# binary_watch_v0.net
KiCad netlist of a schematic drawn in EAGLE
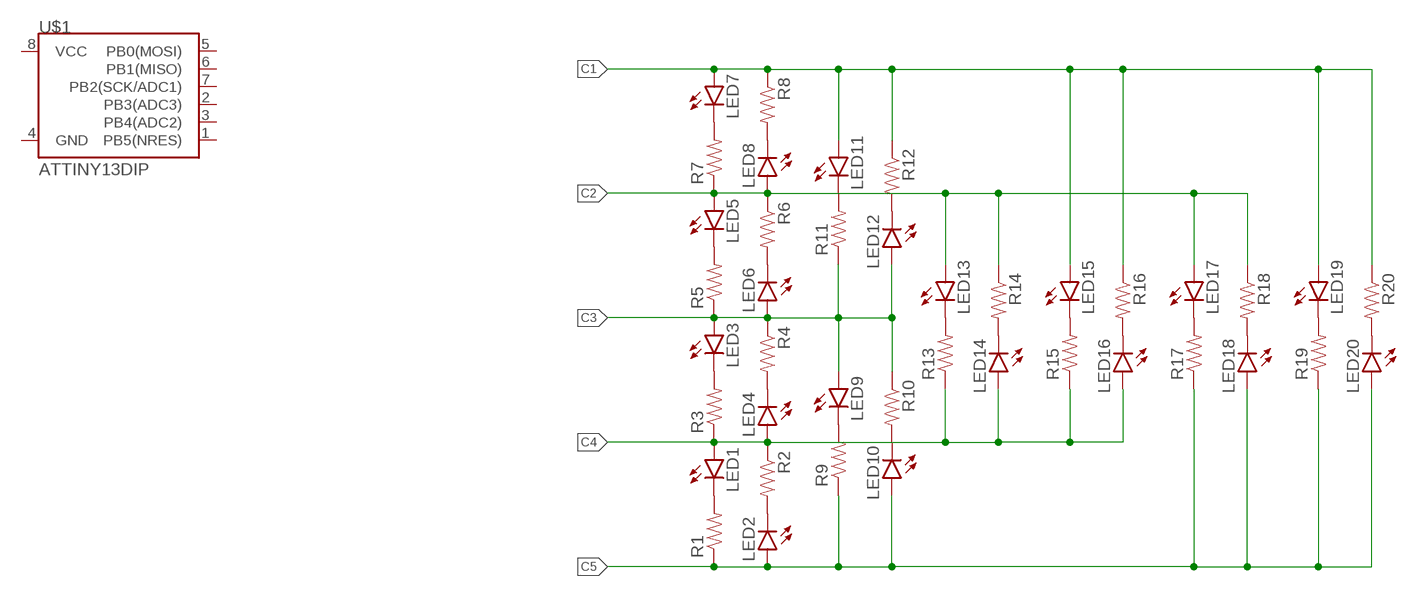
[diagram p0: schematic, sheet 1]

(export (version "E")
  (design (tool "Eeschema 10.0.6"))
  (components
    (comp (ref "LED1")
      (value "LED0603")
      (footprint "eagle-import:LED-0603")
      (libsource (lib "eagle-import") (part "LED0603"))
    )
    (comp (ref "LED2")
      (value "LED0603")
      (footprint "eagle-import:LED-0603")
      (libsource (lib "eagle-import") (part "LED0603"))
    )
    (comp (ref "LED3")
      (value "LED0603")
      (footprint "eagle-import:LED-0603")
      (libsource (lib "eagle-import") (part "LED0603"))
    )
    (comp (ref "LED4")
      (value "LED0603")
      (footprint "eagle-import:LED-0603")
      (libsource (lib "eagle-import") (part "LED0603"))
    )
    (comp (ref "LED5")
      (value "LED0603")
      (footprint "eagle-import:LED-0603")
      (libsource (lib "eagle-import") (part "LED0603"))
    )
    (comp (ref "LED6")
      (value "LED0603")
      (footprint "eagle-import:LED-0603")
      (libsource (lib "eagle-import") (part "LED0603"))
    )
    (comp (ref "LED7")
      (value "LED0603")
      (footprint "eagle-import:LED-0603")
      (libsource (lib "eagle-import") (part "LED0603"))
    )
    (comp (ref "LED8")
      (value "LED0603")
      (footprint "eagle-import:LED-0603")
      (libsource (lib "eagle-import") (part "LED0603"))
    )
    (comp (ref "LED9")
      (value "LED0603")
      (footprint "eagle-import:LED-0603")
      (libsource (lib "eagle-import") (part "LED0603"))
    )
    (comp (ref "LED10")
      (value "LED0603")
      (footprint "eagle-import:LED-0603")
      (libsource (lib "eagle-import") (part "LED0603"))
    )
    (comp (ref "LED11")
      (value "LED0603")
      (footprint "eagle-import:LED-0603")
      (libsource (lib "eagle-import") (part "LED0603"))
    )
    (comp (ref "LED12")
      (value "LED0603")
      (footprint "eagle-import:LED-0603")
      (libsource (lib "eagle-import") (part "LED0603"))
    )
    (comp (ref "LED13")
      (value "LED0603")
      (footprint "eagle-import:LED-0603")
      (libsource (lib "eagle-import") (part "LED0603"))
    )
    (comp (ref "LED14")
      (value "LED0603")
      (footprint "eagle-import:LED-0603")
      (libsource (lib "eagle-import") (part "LED0603"))
    )
    (comp (ref "LED15")
      (value "LED0603")
      (footprint "eagle-import:LED-0603")
      (libsource (lib "eagle-import") (part "LED0603"))
    )
    (comp (ref "LED16")
      (value "LED0603")
      (footprint "eagle-import:LED-0603")
      (libsource (lib "eagle-import") (part "LED0603"))
    )
    (comp (ref "LED17")
      (value "LED0603")
      (footprint "eagle-import:LED-0603")
      (libsource (lib "eagle-import") (part "LED0603"))
    )
    (comp (ref "LED18")
      (value "LED0603")
      (footprint "eagle-import:LED-0603")
      (libsource (lib "eagle-import") (part "LED0603"))
    )
    (comp (ref "LED19")
      (value "LED0603")
      (footprint "eagle-import:LED-0603")
      (libsource (lib "eagle-import") (part "LED0603"))
    )
    (comp (ref "LED20")
      (value "LED0603")
      (footprint "eagle-import:LED-0603")
      (libsource (lib "eagle-import") (part "LED0603"))
    )
    (comp (ref "R1")
      (value "RESISTOR0603-RES")
      (footprint "eagle-import:0603-RES")
      (libsource (lib "eagle-import") (part "RESISTOR0603-RES"))
    )
    (comp (ref "R2")
      (value "RESISTOR0603-RES")
      (footprint "eagle-import:0603-RES")
      (libsource (lib "eagle-import") (part "RESISTOR0603-RES"))
    )
    (comp (ref "R3")
      (value "RESISTOR0603-RES")
      (footprint "eagle-import:0603-RES")
      (libsource (lib "eagle-import") (part "RESISTOR0603-RES"))
    )
    (comp (ref "R4")
      (value "RESISTOR0603-RES")
      (footprint "eagle-import:0603-RES")
      (libsource (lib "eagle-import") (part "RESISTOR0603-RES"))
    )
    (comp (ref "R5")
      (value "RESISTOR0603-RES")
      (footprint "eagle-import:0603-RES")
      (libsource (lib "eagle-import") (part "RESISTOR0603-RES"))
    )
    (comp (ref "R6")
      (value "RESISTOR0603-RES")
      (footprint "eagle-import:0603-RES")
      (libsource (lib "eagle-import") (part "RESISTOR0603-RES"))
    )
    (comp (ref "R7")
      (value "RESISTOR0603-RES")
      (footprint "eagle-import:0603-RES")
      (libsource (lib "eagle-import") (part "RESISTOR0603-RES"))
    )
    (comp (ref "R8")
      (value "RESISTOR0603-RES")
      (footprint "eagle-import:0603-RES")
      (libsource (lib "eagle-import") (part "RESISTOR0603-RES"))
    )
    (comp (ref "R9")
      (value "RESISTOR0603-RES")
      (footprint "eagle-import:0603-RES")
      (libsource (lib "eagle-import") (part "RESISTOR0603-RES"))
    )
    (comp (ref "R10")
      (value "RESISTOR0603-RES")
      (footprint "eagle-import:0603-RES")
      (libsource (lib "eagle-import") (part "RESISTOR0603-RES"))
    )
    (comp (ref "R11")
      (value "RESISTOR0603-RES")
      (footprint "eagle-import:0603-RES")
      (libsource (lib "eagle-import") (part "RESISTOR0603-RES"))
    )
    (comp (ref "R12")
      (value "RESISTOR0603-RES")
      (footprint "eagle-import:0603-RES")
      (libsource (lib "eagle-import") (part "RESISTOR0603-RES"))
    )
    (comp (ref "R13")
      (value "RESISTOR0603-RES")
      (footprint "eagle-import:0603-RES")
      (libsource (lib "eagle-import") (part "RESISTOR0603-RES"))
    )
    (comp (ref "R14")
      (value "RESISTOR0603-RES")
      (footprint "eagle-import:0603-RES")
      (libsource (lib "eagle-import") (part "RESISTOR0603-RES"))
    )
    (comp (ref "R15")
      (value "RESISTOR0603-RES")
      (footprint "eagle-import:0603-RES")
      (libsource (lib "eagle-import") (part "RESISTOR0603-RES"))
    )
    (comp (ref "R16")
      (value "RESISTOR0603-RES")
      (footprint "eagle-import:0603-RES")
      (libsource (lib "eagle-import") (part "RESISTOR0603-RES"))
    )
    (comp (ref "R17")
      (value "RESISTOR0603-RES")
      (footprint "eagle-import:0603-RES")
      (libsource (lib "eagle-import") (part "RESISTOR0603-RES"))
    )
    (comp (ref "R18")
      (value "RESISTOR0603-RES")
      (footprint "eagle-import:0603-RES")
      (libsource (lib "eagle-import") (part "RESISTOR0603-RES"))
    )
    (comp (ref "R19")
      (value "RESISTOR0603-RES")
      (footprint "eagle-import:0603-RES")
      (libsource (lib "eagle-import") (part "RESISTOR0603-RES"))
    )
    (comp (ref "R20")
      (value "RESISTOR0603-RES")
      (footprint "eagle-import:0603-RES")
      (libsource (lib "eagle-import") (part "RESISTOR0603-RES"))
    )
    (comp (ref "U$1")
      (value "ATTINY13DIP")
      (footprint "eagle-import:DIP08")
      (libsource (lib "eagle-import") (part "ATTINY13DIP"))
    )
  )
  (nets
    (net (code "1") (name "C1") (class "Default")
      (node (ref "LED11") (pin "A") (pinfunction "A_A") (pintype "passive"))
      (node (ref "LED15") (pin "A") (pinfunction "A_A") (pintype "passive"))
      (node (ref "LED19") (pin "A") (pinfunction "A_A") (pintype "passive"))
      (node (ref "LED7") (pin "A") (pinfunction "A_A") (pintype "passive"))
      (node (ref "R12") (pin "1") (pinfunction "1_1") (pintype "passive"))
      (node (ref "R16") (pin "1") (pinfunction "1_1") (pintype "passive"))
      (node (ref "R20") (pin "1") (pinfunction "1_1") (pintype "passive"))
      (node (ref "R8") (pin "1") (pinfunction "1_1") (pintype "passive"))
    )
    (net (code "2") (name "C2") (class "Default")
      (node (ref "LED13") (pin "A") (pinfunction "A_A") (pintype "passive"))
      (node (ref "LED17") (pin "A") (pinfunction "A_A") (pintype "passive"))
      (node (ref "LED5") (pin "A") (pinfunction "A_A") (pintype "passive"))
      (node (ref "LED8") (pin "A") (pinfunction "A_A") (pintype "passive"))
      (node (ref "R14") (pin "1") (pinfunction "1_1") (pintype "passive"))
      (node (ref "R18") (pin "1") (pinfunction "1_1") (pintype "passive"))
      (node (ref "R6") (pin "1") (pinfunction "1_1") (pintype "passive"))
      (node (ref "R7") (pin "1") (pinfunction "1_1") (pintype "passive"))
    )
    (net (code "3") (name "C3") (class "Default")
      (node (ref "LED12") (pin "A") (pinfunction "A_A") (pintype "passive"))
      (node (ref "LED3") (pin "A") (pinfunction "A_A") (pintype "passive"))
      (node (ref "LED6") (pin "A") (pinfunction "A_A") (pintype "passive"))
      (node (ref "LED9") (pin "A") (pinfunction "A_A") (pintype "passive"))
      (node (ref "R10") (pin "1") (pinfunction "1_1") (pintype "passive"))
      (node (ref "R11") (pin "1") (pinfunction "1_1") (pintype "passive"))
      (node (ref "R4") (pin "1") (pinfunction "1_1") (pintype "passive"))
      (node (ref "R5") (pin "1") (pinfunction "1_1") (pintype "passive"))
    )
    (net (code "4") (name "C4") (class "Default")
      (node (ref "LED1") (pin "A") (pinfunction "A_A") (pintype "passive"))
      (node (ref "LED14") (pin "A") (pinfunction "A_A") (pintype "passive"))
      (node (ref "LED16") (pin "A") (pinfunction "A_A") (pintype "passive"))
      (node (ref "LED4") (pin "A") (pinfunction "A_A") (pintype "passive"))
      (node (ref "R13") (pin "1") (pinfunction "1_1") (pintype "passive"))
      (node (ref "R15") (pin "1") (pinfunction "1_1") (pintype "passive"))
      (node (ref "R2") (pin "1") (pinfunction "1_1") (pintype "passive"))
      (node (ref "R3") (pin "1") (pinfunction "1_1") (pintype "passive"))
    )
    (net (code "5") (name "C5") (class "Default")
      (node (ref "LED10") (pin "A") (pinfunction "A_A") (pintype "passive"))
      (node (ref "LED18") (pin "A") (pinfunction "A_A") (pintype "passive"))
      (node (ref "LED2") (pin "A") (pinfunction "A_A") (pintype "passive"))
      (node (ref "LED20") (pin "A") (pinfunction "A_A") (pintype "passive"))
      (node (ref "R1") (pin "1") (pinfunction "1_1") (pintype "passive"))
      (node (ref "R17") (pin "1") (pinfunction "1_1") (pintype "passive"))
      (node (ref "R19") (pin "1") (pinfunction "1_1") (pintype "passive"))
      (node (ref "R9") (pin "1") (pinfunction "1_1") (pintype "passive"))
    )
    (net (code "6") (name "Net-(LED1-PadC)") (class "Default")
      (node (ref "LED1") (pin "C") (pinfunction "C_C") (pintype "passive"))
      (node (ref "R1") (pin "2") (pinfunction "2_2") (pintype "passive"))
    )
    (net (code "7") (name "Net-(LED2-PadC)") (class "Default")
      (node (ref "LED2") (pin "C") (pinfunction "C_C") (pintype "passive"))
      (node (ref "R2") (pin "2") (pinfunction "2_2") (pintype "passive"))
    )
    (net (code "8") (name "Net-(LED3-PadC)") (class "Default")
      (node (ref "LED3") (pin "C") (pinfunction "C_C") (pintype "passive"))
      (node (ref "R3") (pin "2") (pinfunction "2_2") (pintype "passive"))
    )
    (net (code "9") (name "Net-(LED4-PadC)") (class "Default")
      (node (ref "LED4") (pin "C") (pinfunction "C_C") (pintype "passive"))
      (node (ref "R4") (pin "2") (pinfunction "2_2") (pintype "passive"))
    )
    (net (code "10") (name "Net-(LED5-PadC)") (class "Default")
      (node (ref "LED5") (pin "C") (pinfunction "C_C") (pintype "passive"))
      (node (ref "R5") (pin "2") (pinfunction "2_2") (pintype "passive"))
    )
    (net (code "11") (name "Net-(LED6-PadC)") (class "Default")
      (node (ref "LED6") (pin "C") (pinfunction "C_C") (pintype "passive"))
      (node (ref "R6") (pin "2") (pinfunction "2_2") (pintype "passive"))
    )
    (net (code "12") (name "Net-(LED7-PadC)") (class "Default")
      (node (ref "LED7") (pin "C") (pinfunction "C_C") (pintype "passive"))
      (node (ref "R7") (pin "2") (pinfunction "2_2") (pintype "passive"))
    )
    (net (code "13") (name "Net-(LED8-PadC)") (class "Default")
      (node (ref "LED8") (pin "C") (pinfunction "C_C") (pintype "passive"))
      (node (ref "R8") (pin "2") (pinfunction "2_2") (pintype "passive"))
    )
    (net (code "14") (name "Net-(LED9-PadC)") (class "Default")
      (node (ref "LED9") (pin "C") (pinfunction "C_C") (pintype "passive"))
      (node (ref "R9") (pin "2") (pinfunction "2_2") (pintype "passive"))
    )
    (net (code "15") (name "Net-(LED10-PadC)") (class "Default")
      (node (ref "LED10") (pin "C") (pinfunction "C_C") (pintype "passive"))
      (node (ref "R10") (pin "2") (pinfunction "2_2") (pintype "passive"))
    )
    (net (code "16") (name "Net-(LED11-PadC)") (class "Default")
      (node (ref "LED11") (pin "C") (pinfunction "C_C") (pintype "passive"))
      (node (ref "R11") (pin "2") (pinfunction "2_2") (pintype "passive"))
    )
    (net (code "17") (name "Net-(LED12-PadC)") (class "Default")
      (node (ref "LED12") (pin "C") (pinfunction "C_C") (pintype "passive"))
      (node (ref "R12") (pin "2") (pinfunction "2_2") (pintype "passive"))
    )
    (net (code "18") (name "Net-(LED13-PadC)") (class "Default")
      (node (ref "LED13") (pin "C") (pinfunction "C_C") (pintype "passive"))
      (node (ref "R13") (pin "2") (pinfunction "2_2") (pintype "passive"))
    )
    (net (code "19") (name "Net-(LED14-PadC)") (class "Default")
      (node (ref "LED14") (pin "C") (pinfunction "C_C") (pintype "passive"))
      (node (ref "R14") (pin "2") (pinfunction "2_2") (pintype "passive"))
    )
    (net (code "20") (name "Net-(LED15-PadC)") (class "Default")
      (node (ref "LED15") (pin "C") (pinfunction "C_C") (pintype "passive"))
      (node (ref "R15") (pin "2") (pinfunction "2_2") (pintype "passive"))
    )
    (net (code "21") (name "Net-(LED16-PadC)") (class "Default")
      (node (ref "LED16") (pin "C") (pinfunction "C_C") (pintype "passive"))
      (node (ref "R16") (pin "2") (pinfunction "2_2") (pintype "passive"))
    )
    (net (code "22") (name "Net-(LED17-PadC)") (class "Default")
      (node (ref "LED17") (pin "C") (pinfunction "C_C") (pintype "passive"))
      (node (ref "R17") (pin "2") (pinfunction "2_2") (pintype "passive"))
    )
    (net (code "23") (name "Net-(LED18-PadC)") (class "Default")
      (node (ref "LED18") (pin "C") (pinfunction "C_C") (pintype "passive"))
      (node (ref "R18") (pin "2") (pinfunction "2_2") (pintype "passive"))
    )
    (net (code "24") (name "Net-(LED19-PadC)") (class "Default")
      (node (ref "LED19") (pin "C") (pinfunction "C_C") (pintype "passive"))
      (node (ref "R19") (pin "2") (pinfunction "2_2") (pintype "passive"))
    )
    (net (code "25") (name "Net-(LED20-PadC)") (class "Default")
      (node (ref "LED20") (pin "C") (pinfunction "C_C") (pintype "passive"))
      (node (ref "R20") (pin "2") (pinfunction "2_2") (pintype "passive"))
    )
    (net (code "26") (name "unconnected-(U$1-GND-Pad4)") (class "Default")
      (node (ref "U$1") (pin "4") (pinfunction "GND_4") (pintype "bidirectional"))
    )
    (net (code "27") (name "unconnected-(U$1-PB0(MOSI)-Pad5)") (class "Default")
      (node (ref "U$1") (pin "5") (pinfunction "PB0(MOSI)_5") (pintype "bidirectional"))
    )
    (net (code "28") (name "unconnected-(U$1-PB1(MISO)-Pad6)") (class "Default")
      (node (ref "U$1") (pin "6") (pinfunction "PB1(MISO)_6") (pintype "bidirectional"))
    )
    (net (code "29") (name "unconnected-(U$1-PB2(SCK{slash}ADC1)-Pad7)") (class "Default")
      (node (ref "U$1") (pin "7") (pinfunction "PB2(SCK/ADC1)_7") (pintype "bidirectional"))
    )
    (net (code "30") (name "unconnected-(U$1-PB3(ADC3)-Pad2)") (class "Default")
      (node (ref "U$1") (pin "2") (pinfunction "PB3(ADC3)_2") (pintype "bidirectional"))
    )
    (net (code "31") (name "unconnected-(U$1-PB4(ADC2)-Pad3)") (class "Default")
      (node (ref "U$1") (pin "3") (pinfunction "PB4(ADC2)_3") (pintype "bidirectional"))
    )
    (net (code "32") (name "unconnected-(U$1-PB5(NRES)-Pad1)") (class "Default")
      (node (ref "U$1") (pin "1") (pinfunction "PB5(NRES)_1") (pintype "bidirectional"))
    )
    (net (code "33") (name "unconnected-(U$1-VCC-Pad8)") (class "Default")
      (node (ref "U$1") (pin "8") (pinfunction "VCC_8") (pintype "bidirectional"))
    )
  )
)
